# CurrentSensorAC712-30_multi.net
KiCad netlist of a schematic drawn in EAGLE
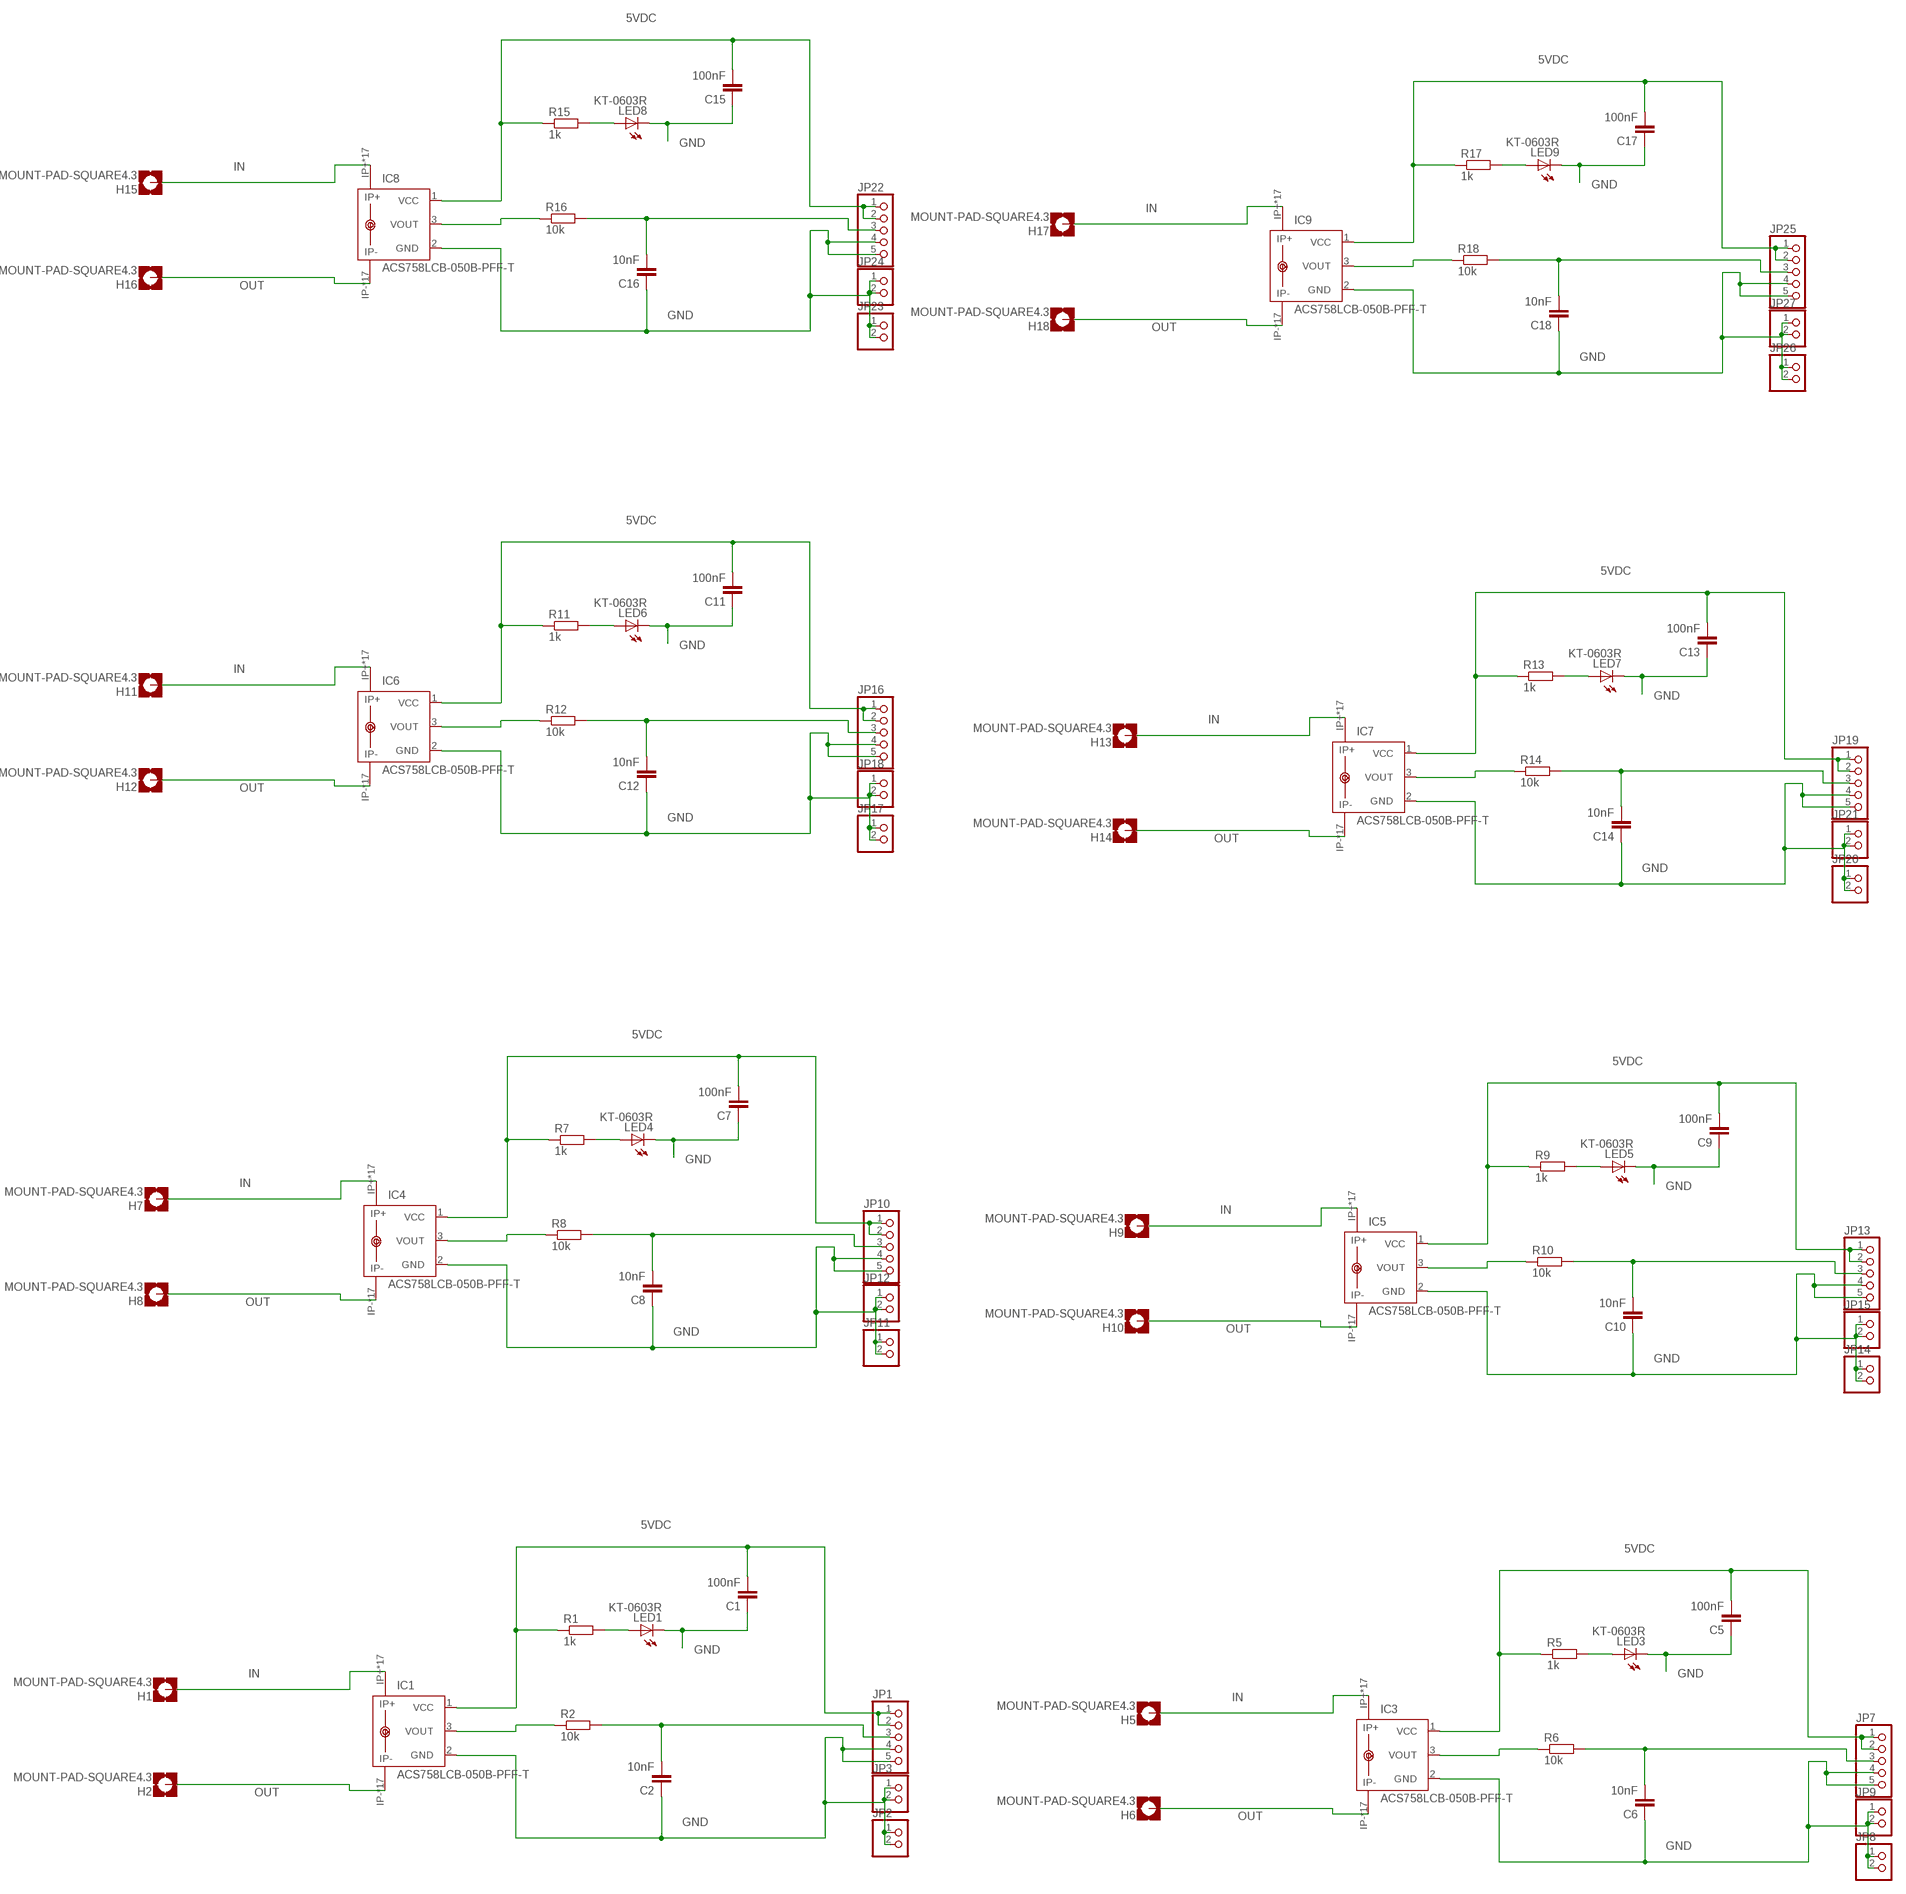
[diagram p0: schematic, sheet 1]

(export (version "E")
  (design (tool "Eeschema 10.0.6"))
  (components
    (comp (ref "C1")
      (value "100nF")
      (footprint "eagle-import:C0805")
      (libsource (lib "eagle-import") (part "C-EUC0805"))
    )
    (comp (ref "C2")
      (value "10nF")
      (footprint "eagle-import:C0805")
      (libsource (lib "eagle-import") (part "C-EUC0805"))
    )
    (comp (ref "C5")
      (value "100nF")
      (footprint "eagle-import:C0805")
      (libsource (lib "eagle-import") (part "C-EUC0805"))
    )
    (comp (ref "C6")
      (value "10nF")
      (footprint "eagle-import:C0805")
      (libsource (lib "eagle-import") (part "C-EUC0805"))
    )
    (comp (ref "C7")
      (value "100nF")
      (footprint "eagle-import:C0805")
      (libsource (lib "eagle-import") (part "C-EUC0805"))
    )
    (comp (ref "C8")
      (value "10nF")
      (footprint "eagle-import:C0805")
      (libsource (lib "eagle-import") (part "C-EUC0805"))
    )
    (comp (ref "C9")
      (value "100nF")
      (footprint "eagle-import:C0805")
      (libsource (lib "eagle-import") (part "C-EUC0805"))
    )
    (comp (ref "C10")
      (value "10nF")
      (footprint "eagle-import:C0805")
      (libsource (lib "eagle-import") (part "C-EUC0805"))
    )
    (comp (ref "C11")
      (value "100nF")
      (footprint "eagle-import:C0805")
      (libsource (lib "eagle-import") (part "C-EUC0805"))
    )
    (comp (ref "C12")
      (value "10nF")
      (footprint "eagle-import:C0805")
      (libsource (lib "eagle-import") (part "C-EUC0805"))
    )
    (comp (ref "C13")
      (value "100nF")
      (footprint "eagle-import:C0805")
      (libsource (lib "eagle-import") (part "C-EUC0805"))
    )
    (comp (ref "C14")
      (value "10nF")
      (footprint "eagle-import:C0805")
      (libsource (lib "eagle-import") (part "C-EUC0805"))
    )
    (comp (ref "C15")
      (value "100nF")
      (footprint "eagle-import:C0805")
      (libsource (lib "eagle-import") (part "C-EUC0805"))
    )
    (comp (ref "C16")
      (value "10nF")
      (footprint "eagle-import:C0805")
      (libsource (lib "eagle-import") (part "C-EUC0805"))
    )
    (comp (ref "C17")
      (value "100nF")
      (footprint "eagle-import:C0805")
      (libsource (lib "eagle-import") (part "C-EUC0805"))
    )
    (comp (ref "C18")
      (value "10nF")
      (footprint "eagle-import:C0805")
      (libsource (lib "eagle-import") (part "C-EUC0805"))
    )
    (comp (ref "H1")
      (value "MOUNT-PAD-SQUARE4.3")
      (footprint "eagle-import:4,3-PAD-SQUARE")
      (libsource (lib "eagle-import") (part "MOUNT-PAD-SQUARE4.3"))
    )
    (comp (ref "H2")
      (value "MOUNT-PAD-SQUARE4.3")
      (footprint "eagle-import:4,3-PAD-SQUARE")
      (libsource (lib "eagle-import") (part "MOUNT-PAD-SQUARE4.3"))
    )
    (comp (ref "H5")
      (value "MOUNT-PAD-SQUARE4.3")
      (footprint "eagle-import:4,3-PAD-SQUARE")
      (libsource (lib "eagle-import") (part "MOUNT-PAD-SQUARE4.3"))
    )
    (comp (ref "H6")
      (value "MOUNT-PAD-SQUARE4.3")
      (footprint "eagle-import:4,3-PAD-SQUARE")
      (libsource (lib "eagle-import") (part "MOUNT-PAD-SQUARE4.3"))
    )
    (comp (ref "H7")
      (value "MOUNT-PAD-SQUARE4.3")
      (footprint "eagle-import:4,3-PAD-SQUARE")
      (libsource (lib "eagle-import") (part "MOUNT-PAD-SQUARE4.3"))
    )
    (comp (ref "H8")
      (value "MOUNT-PAD-SQUARE4.3")
      (footprint "eagle-import:4,3-PAD-SQUARE")
      (libsource (lib "eagle-import") (part "MOUNT-PAD-SQUARE4.3"))
    )
    (comp (ref "H9")
      (value "MOUNT-PAD-SQUARE4.3")
      (footprint "eagle-import:4,3-PAD-SQUARE")
      (libsource (lib "eagle-import") (part "MOUNT-PAD-SQUARE4.3"))
    )
    (comp (ref "H10")
      (value "MOUNT-PAD-SQUARE4.3")
      (footprint "eagle-import:4,3-PAD-SQUARE")
      (libsource (lib "eagle-import") (part "MOUNT-PAD-SQUARE4.3"))
    )
    (comp (ref "H11")
      (value "MOUNT-PAD-SQUARE4.3")
      (footprint "eagle-import:4,3-PAD-SQUARE")
      (libsource (lib "eagle-import") (part "MOUNT-PAD-SQUARE4.3"))
    )
    (comp (ref "H12")
      (value "MOUNT-PAD-SQUARE4.3")
      (footprint "eagle-import:4,3-PAD-SQUARE")
      (libsource (lib "eagle-import") (part "MOUNT-PAD-SQUARE4.3"))
    )
    (comp (ref "H13")
      (value "MOUNT-PAD-SQUARE4.3")
      (footprint "eagle-import:4,3-PAD-SQUARE")
      (libsource (lib "eagle-import") (part "MOUNT-PAD-SQUARE4.3"))
    )
    (comp (ref "H14")
      (value "MOUNT-PAD-SQUARE4.3")
      (footprint "eagle-import:4,3-PAD-SQUARE")
      (libsource (lib "eagle-import") (part "MOUNT-PAD-SQUARE4.3"))
    )
    (comp (ref "H15")
      (value "MOUNT-PAD-SQUARE4.3")
      (footprint "eagle-import:4,3-PAD-SQUARE")
      (libsource (lib "eagle-import") (part "MOUNT-PAD-SQUARE4.3"))
    )
    (comp (ref "H16")
      (value "MOUNT-PAD-SQUARE4.3")
      (footprint "eagle-import:4,3-PAD-SQUARE")
      (libsource (lib "eagle-import") (part "MOUNT-PAD-SQUARE4.3"))
    )
    (comp (ref "H17")
      (value "MOUNT-PAD-SQUARE4.3")
      (footprint "eagle-import:4,3-PAD-SQUARE")
      (libsource (lib "eagle-import") (part "MOUNT-PAD-SQUARE4.3"))
    )
    (comp (ref "H18")
      (value "MOUNT-PAD-SQUARE4.3")
      (footprint "eagle-import:4,3-PAD-SQUARE")
      (libsource (lib "eagle-import") (part "MOUNT-PAD-SQUARE4.3"))
    )
    (comp (ref "IC1")
      (value "ACS758LCB-050B-PFF-T")
      (footprint "eagle-import:CB-PFF")
      (libsource (lib "eagle-import") (part "ACS758LCB-050B-PFF-T"))
    )
    (comp (ref "IC3")
      (value "ACS758LCB-050B-PFF-T")
      (footprint "eagle-import:CB-PFF")
      (libsource (lib "eagle-import") (part "ACS758LCB-050B-PFF-T"))
    )
    (comp (ref "IC4")
      (value "ACS758LCB-050B-PFF-T")
      (footprint "eagle-import:CB-PFF")
      (libsource (lib "eagle-import") (part "ACS758LCB-050B-PFF-T"))
    )
    (comp (ref "IC5")
      (value "ACS758LCB-050B-PFF-T")
      (footprint "eagle-import:CB-PFF")
      (libsource (lib "eagle-import") (part "ACS758LCB-050B-PFF-T"))
    )
    (comp (ref "IC6")
      (value "ACS758LCB-050B-PFF-T")
      (footprint "eagle-import:CB-PFF")
      (libsource (lib "eagle-import") (part "ACS758LCB-050B-PFF-T"))
    )
    (comp (ref "IC7")
      (value "ACS758LCB-050B-PFF-T")
      (footprint "eagle-import:CB-PFF")
      (libsource (lib "eagle-import") (part "ACS758LCB-050B-PFF-T"))
    )
    (comp (ref "IC8")
      (value "ACS758LCB-050B-PFF-T")
      (footprint "eagle-import:CB-PFF")
      (libsource (lib "eagle-import") (part "ACS758LCB-050B-PFF-T"))
    )
    (comp (ref "IC9")
      (value "ACS758LCB-050B-PFF-T")
      (footprint "eagle-import:CB-PFF")
      (libsource (lib "eagle-import") (part "ACS758LCB-050B-PFF-T"))
    )
    (comp (ref "JP1")
      (value "PINHD-1X5")
      (footprint "eagle-import:1X05")
      (libsource (lib "eagle-import") (part "PINHD-1X5"))
    )
    (comp (ref "JP2")
      (value "PINHD-1X2")
      (footprint "eagle-import:1X02")
      (libsource (lib "eagle-import") (part "PINHD-1X2"))
    )
    (comp (ref "JP3")
      (value "PINHD-1X2")
      (footprint "eagle-import:1X02")
      (libsource (lib "eagle-import") (part "PINHD-1X2"))
    )
    (comp (ref "JP7")
      (value "PINHD-1X5")
      (footprint "eagle-import:1X05")
      (libsource (lib "eagle-import") (part "PINHD-1X5"))
    )
    (comp (ref "JP8")
      (value "PINHD-1X2")
      (footprint "eagle-import:1X02")
      (libsource (lib "eagle-import") (part "PINHD-1X2"))
    )
    (comp (ref "JP9")
      (value "PINHD-1X2")
      (footprint "eagle-import:1X02")
      (libsource (lib "eagle-import") (part "PINHD-1X2"))
    )
    (comp (ref "JP10")
      (value "PINHD-1X5")
      (footprint "eagle-import:1X05")
      (libsource (lib "eagle-import") (part "PINHD-1X5"))
    )
    (comp (ref "JP11")
      (value "PINHD-1X2")
      (footprint "eagle-import:1X02")
      (libsource (lib "eagle-import") (part "PINHD-1X2"))
    )
    (comp (ref "JP12")
      (value "PINHD-1X2")
      (footprint "eagle-import:1X02")
      (libsource (lib "eagle-import") (part "PINHD-1X2"))
    )
    (comp (ref "JP13")
      (value "PINHD-1X5")
      (footprint "eagle-import:1X05")
      (libsource (lib "eagle-import") (part "PINHD-1X5"))
    )
    (comp (ref "JP14")
      (value "PINHD-1X2")
      (footprint "eagle-import:1X02")
      (libsource (lib "eagle-import") (part "PINHD-1X2"))
    )
    (comp (ref "JP15")
      (value "PINHD-1X2")
      (footprint "eagle-import:1X02")
      (libsource (lib "eagle-import") (part "PINHD-1X2"))
    )
    (comp (ref "JP16")
      (value "PINHD-1X5")
      (footprint "eagle-import:1X05")
      (libsource (lib "eagle-import") (part "PINHD-1X5"))
    )
    (comp (ref "JP17")
      (value "PINHD-1X2")
      (footprint "eagle-import:1X02")
      (libsource (lib "eagle-import") (part "PINHD-1X2"))
    )
    (comp (ref "JP18")
      (value "PINHD-1X2")
      (footprint "eagle-import:1X02")
      (libsource (lib "eagle-import") (part "PINHD-1X2"))
    )
    (comp (ref "JP19")
      (value "PINHD-1X5")
      (footprint "eagle-import:1X05")
      (libsource (lib "eagle-import") (part "PINHD-1X5"))
    )
    (comp (ref "JP20")
      (value "PINHD-1X2")
      (footprint "eagle-import:1X02")
      (libsource (lib "eagle-import") (part "PINHD-1X2"))
    )
    (comp (ref "JP21")
      (value "PINHD-1X2")
      (footprint "eagle-import:1X02")
      (libsource (lib "eagle-import") (part "PINHD-1X2"))
    )
    (comp (ref "JP22")
      (value "PINHD-1X5")
      (footprint "eagle-import:1X05")
      (libsource (lib "eagle-import") (part "PINHD-1X5"))
    )
    (comp (ref "JP23")
      (value "PINHD-1X2")
      (footprint "eagle-import:1X02")
      (libsource (lib "eagle-import") (part "PINHD-1X2"))
    )
    (comp (ref "JP24")
      (value "PINHD-1X2")
      (footprint "eagle-import:1X02")
      (libsource (lib "eagle-import") (part "PINHD-1X2"))
    )
    (comp (ref "JP25")
      (value "PINHD-1X5")
      (footprint "eagle-import:1X05")
      (libsource (lib "eagle-import") (part "PINHD-1X5"))
    )
    (comp (ref "JP26")
      (value "PINHD-1X2")
      (footprint "eagle-import:1X02")
      (libsource (lib "eagle-import") (part "PINHD-1X2"))
    )
    (comp (ref "JP27")
      (value "PINHD-1X2")
      (footprint "eagle-import:1X02")
      (libsource (lib "eagle-import") (part "PINHD-1X2"))
    )
    (comp (ref "LED1")
      (value "KT-0603R")
      (footprint "eagle-import:CHIPLED_0603")
      (libsource (lib "eagle-import") (part "LEDCHIPLED_0603"))
    )
    (comp (ref "LED3")
      (value "KT-0603R")
      (footprint "eagle-import:CHIPLED_0603")
      (libsource (lib "eagle-import") (part "LEDCHIPLED_0603"))
    )
    (comp (ref "LED4")
      (value "KT-0603R")
      (footprint "eagle-import:CHIPLED_0603")
      (libsource (lib "eagle-import") (part "LEDCHIPLED_0603"))
    )
    (comp (ref "LED5")
      (value "KT-0603R")
      (footprint "eagle-import:CHIPLED_0603")
      (libsource (lib "eagle-import") (part "LEDCHIPLED_0603"))
    )
    (comp (ref "LED6")
      (value "KT-0603R")
      (footprint "eagle-import:CHIPLED_0603")
      (libsource (lib "eagle-import") (part "LEDCHIPLED_0603"))
    )
    (comp (ref "LED7")
      (value "KT-0603R")
      (footprint "eagle-import:CHIPLED_0603")
      (libsource (lib "eagle-import") (part "LEDCHIPLED_0603"))
    )
    (comp (ref "LED8")
      (value "KT-0603R")
      (footprint "eagle-import:CHIPLED_0603")
      (libsource (lib "eagle-import") (part "LEDCHIPLED_0603"))
    )
    (comp (ref "LED9")
      (value "KT-0603R")
      (footprint "eagle-import:CHIPLED_0603")
      (libsource (lib "eagle-import") (part "LEDCHIPLED_0603"))
    )
    (comp (ref "R1")
      (value "1k")
      (footprint "eagle-import:R0805")
      (libsource (lib "eagle-import") (part "R-EU_R0805"))
    )
    (comp (ref "R2")
      (value "10k")
      (footprint "eagle-import:R0805")
      (libsource (lib "eagle-import") (part "R-EU_R0805"))
    )
    (comp (ref "R5")
      (value "1k")
      (footprint "eagle-import:R0805")
      (libsource (lib "eagle-import") (part "R-EU_R0805"))
    )
    (comp (ref "R6")
      (value "10k")
      (footprint "eagle-import:R0805")
      (libsource (lib "eagle-import") (part "R-EU_R0805"))
    )
    (comp (ref "R7")
      (value "1k")
      (footprint "eagle-import:R0805")
      (libsource (lib "eagle-import") (part "R-EU_R0805"))
    )
    (comp (ref "R8")
      (value "10k")
      (footprint "eagle-import:R0805")
      (libsource (lib "eagle-import") (part "R-EU_R0805"))
    )
    (comp (ref "R9")
      (value "1k")
      (footprint "eagle-import:R0805")
      (libsource (lib "eagle-import") (part "R-EU_R0805"))
    )
    (comp (ref "R10")
      (value "10k")
      (footprint "eagle-import:R0805")
      (libsource (lib "eagle-import") (part "R-EU_R0805"))
    )
    (comp (ref "R11")
      (value "1k")
      (footprint "eagle-import:R0805")
      (libsource (lib "eagle-import") (part "R-EU_R0805"))
    )
    (comp (ref "R12")
      (value "10k")
      (footprint "eagle-import:R0805")
      (libsource (lib "eagle-import") (part "R-EU_R0805"))
    )
    (comp (ref "R13")
      (value "1k")
      (footprint "eagle-import:R0805")
      (libsource (lib "eagle-import") (part "R-EU_R0805"))
    )
    (comp (ref "R14")
      (value "10k")
      (footprint "eagle-import:R0805")
      (libsource (lib "eagle-import") (part "R-EU_R0805"))
    )
    (comp (ref "R15")
      (value "1k")
      (footprint "eagle-import:R0805")
      (libsource (lib "eagle-import") (part "R-EU_R0805"))
    )
    (comp (ref "R16")
      (value "10k")
      (footprint "eagle-import:R0805")
      (libsource (lib "eagle-import") (part "R-EU_R0805"))
    )
    (comp (ref "R17")
      (value "1k")
      (footprint "eagle-import:R0805")
      (libsource (lib "eagle-import") (part "R-EU_R0805"))
    )
    (comp (ref "R18")
      (value "10k")
      (footprint "eagle-import:R0805")
      (libsource (lib "eagle-import") (part "R-EU_R0805"))
    )
  )
  (nets
    (net (code "1") (name "/5VDC") (class "Default")
      (node (ref "C1") (pin "2") (pinfunction "2_2") (pintype "passive"))
      (node (ref "C11") (pin "2") (pinfunction "2_2") (pintype "passive"))
      (node (ref "C13") (pin "2") (pinfunction "2_2") (pintype "passive"))
      (node (ref "C15") (pin "2") (pinfunction "2_2") (pintype "passive"))
      (node (ref "C17") (pin "2") (pinfunction "2_2") (pintype "passive"))
      (node (ref "C5") (pin "2") (pinfunction "2_2") (pintype "passive"))
      (node (ref "C7") (pin "2") (pinfunction "2_2") (pintype "passive"))
      (node (ref "C9") (pin "2") (pinfunction "2_2") (pintype "passive"))
      (node (ref "IC1") (pin "1") (pinfunction "VCC_1") (pintype "power_in"))
      (node (ref "IC3") (pin "1") (pinfunction "VCC_1") (pintype "power_in"))
      (node (ref "IC4") (pin "1") (pinfunction "VCC_1") (pintype "power_in"))
      (node (ref "IC5") (pin "1") (pinfunction "VCC_1") (pintype "power_in"))
      (node (ref "IC6") (pin "1") (pinfunction "VCC_1") (pintype "power_in"))
      (node (ref "IC7") (pin "1") (pinfunction "VCC_1") (pintype "power_in"))
      (node (ref "IC8") (pin "1") (pinfunction "VCC_1") (pintype "power_in"))
      (node (ref "IC9") (pin "1") (pinfunction "VCC_1") (pintype "power_in"))
      (node (ref "JP1") (pin "1") (pinfunction "1_1") (pintype "passive"))
      (node (ref "JP1") (pin "2") (pinfunction "2_2") (pintype "passive"))
      (node (ref "JP10") (pin "1") (pinfunction "1_1") (pintype "passive"))
      (node (ref "JP10") (pin "2") (pinfunction "2_2") (pintype "passive"))
      (node (ref "JP13") (pin "1") (pinfunction "1_1") (pintype "passive"))
      (node (ref "JP13") (pin "2") (pinfunction "2_2") (pintype "passive"))
      (node (ref "JP16") (pin "1") (pinfunction "1_1") (pintype "passive"))
      (node (ref "JP16") (pin "2") (pinfunction "2_2") (pintype "passive"))
      (node (ref "JP19") (pin "1") (pinfunction "1_1") (pintype "passive"))
      (node (ref "JP19") (pin "2") (pinfunction "2_2") (pintype "passive"))
      (node (ref "JP22") (pin "1") (pinfunction "1_1") (pintype "passive"))
      (node (ref "JP22") (pin "2") (pinfunction "2_2") (pintype "passive"))
      (node (ref "JP25") (pin "1") (pinfunction "1_1") (pintype "passive"))
      (node (ref "JP25") (pin "2") (pinfunction "2_2") (pintype "passive"))
      (node (ref "JP7") (pin "1") (pinfunction "1_1") (pintype "passive"))
      (node (ref "JP7") (pin "2") (pinfunction "2_2") (pintype "passive"))
      (node (ref "R1") (pin "1") (pinfunction "1_1") (pintype "passive"))
      (node (ref "R11") (pin "1") (pinfunction "1_1") (pintype "passive"))
      (node (ref "R13") (pin "1") (pinfunction "1_1") (pintype "passive"))
      (node (ref "R15") (pin "1") (pinfunction "1_1") (pintype "passive"))
      (node (ref "R17") (pin "1") (pinfunction "1_1") (pintype "passive"))
      (node (ref "R5") (pin "1") (pinfunction "1_1") (pintype "passive"))
      (node (ref "R7") (pin "1") (pinfunction "1_1") (pintype "passive"))
      (node (ref "R9") (pin "1") (pinfunction "1_1") (pintype "passive"))
    )
    (net (code "2") (name "/GND") (class "Default")
      (node (ref "C1") (pin "1") (pinfunction "1_1") (pintype "passive"))
      (node (ref "C10") (pin "1") (pinfunction "1_1") (pintype "passive"))
      (node (ref "C11") (pin "1") (pinfunction "1_1") (pintype "passive"))
      (node (ref "C12") (pin "1") (pinfunction "1_1") (pintype "passive"))
      (node (ref "C13") (pin "1") (pinfunction "1_1") (pintype "passive"))
      (node (ref "C14") (pin "1") (pinfunction "1_1") (pintype "passive"))
      (node (ref "C15") (pin "1") (pinfunction "1_1") (pintype "passive"))
      (node (ref "C16") (pin "1") (pinfunction "1_1") (pintype "passive"))
      (node (ref "C17") (pin "1") (pinfunction "1_1") (pintype "passive"))
      (node (ref "C18") (pin "1") (pinfunction "1_1") (pintype "passive"))
      (node (ref "C2") (pin "1") (pinfunction "1_1") (pintype "passive"))
      (node (ref "C5") (pin "1") (pinfunction "1_1") (pintype "passive"))
      (node (ref "C6") (pin "1") (pinfunction "1_1") (pintype "passive"))
      (node (ref "C7") (pin "1") (pinfunction "1_1") (pintype "passive"))
      (node (ref "C8") (pin "1") (pinfunction "1_1") (pintype "passive"))
      (node (ref "C9") (pin "1") (pinfunction "1_1") (pintype "passive"))
      (node (ref "IC1") (pin "2") (pinfunction "GND_2") (pintype "power_in"))
      (node (ref "IC3") (pin "2") (pinfunction "GND_2") (pintype "power_in"))
      (node (ref "IC4") (pin "2") (pinfunction "GND_2") (pintype "power_in"))
      (node (ref "IC5") (pin "2") (pinfunction "GND_2") (pintype "power_in"))
      (node (ref "IC6") (pin "2") (pinfunction "GND_2") (pintype "power_in"))
      (node (ref "IC7") (pin "2") (pinfunction "GND_2") (pintype "power_in"))
      (node (ref "IC8") (pin "2") (pinfunction "GND_2") (pintype "power_in"))
      (node (ref "IC9") (pin "2") (pinfunction "GND_2") (pintype "power_in"))
      (node (ref "JP1") (pin "4") (pinfunction "4_4") (pintype "passive"))
      (node (ref "JP1") (pin "5") (pinfunction "5_5") (pintype "passive"))
      (node (ref "JP10") (pin "4") (pinfunction "4_4") (pintype "passive"))
      (node (ref "JP10") (pin "5") (pinfunction "5_5") (pintype "passive"))
      (node (ref "JP11") (pin "1") (pinfunction "1_1") (pintype "passive"))
      (node (ref "JP11") (pin "2") (pinfunction "2_2") (pintype "passive"))
      (node (ref "JP12") (pin "1") (pinfunction "1_1") (pintype "passive"))
      (node (ref "JP12") (pin "2") (pinfunction "2_2") (pintype "passive"))
      (node (ref "JP13") (pin "4") (pinfunction "4_4") (pintype "passive"))
      (node (ref "JP13") (pin "5") (pinfunction "5_5") (pintype "passive"))
      (node (ref "JP14") (pin "1") (pinfunction "1_1") (pintype "passive"))
      (node (ref "JP14") (pin "2") (pinfunction "2_2") (pintype "passive"))
      (node (ref "JP15") (pin "1") (pinfunction "1_1") (pintype "passive"))
      (node (ref "JP15") (pin "2") (pinfunction "2_2") (pintype "passive"))
      (node (ref "JP16") (pin "4") (pinfunction "4_4") (pintype "passive"))
      (node (ref "JP16") (pin "5") (pinfunction "5_5") (pintype "passive"))
      (node (ref "JP17") (pin "1") (pinfunction "1_1") (pintype "passive"))
      (node (ref "JP17") (pin "2") (pinfunction "2_2") (pintype "passive"))
      (node (ref "JP18") (pin "1") (pinfunction "1_1") (pintype "passive"))
      (node (ref "JP18") (pin "2") (pinfunction "2_2") (pintype "passive"))
      (node (ref "JP19") (pin "4") (pinfunction "4_4") (pintype "passive"))
      (node (ref "JP19") (pin "5") (pinfunction "5_5") (pintype "passive"))
      (node (ref "JP2") (pin "1") (pinfunction "1_1") (pintype "passive"))
      (node (ref "JP2") (pin "2") (pinfunction "2_2") (pintype "passive"))
      (node (ref "JP20") (pin "1") (pinfunction "1_1") (pintype "passive"))
      (node (ref "JP20") (pin "2") (pinfunction "2_2") (pintype "passive"))
      (node (ref "JP21") (pin "1") (pinfunction "1_1") (pintype "passive"))
      (node (ref "JP21") (pin "2") (pinfunction "2_2") (pintype "passive"))
      (node (ref "JP22") (pin "4") (pinfunction "4_4") (pintype "passive"))
      (node (ref "JP22") (pin "5") (pinfunction "5_5") (pintype "passive"))
      (node (ref "JP23") (pin "1") (pinfunction "1_1") (pintype "passive"))
      (node (ref "JP23") (pin "2") (pinfunction "2_2") (pintype "passive"))
      (node (ref "JP24") (pin "1") (pinfunction "1_1") (pintype "passive"))
      (node (ref "JP24") (pin "2") (pinfunction "2_2") (pintype "passive"))
      (node (ref "JP25") (pin "4") (pinfunction "4_4") (pintype "passive"))
      (node (ref "JP25") (pin "5") (pinfunction "5_5") (pintype "passive"))
      (node (ref "JP26") (pin "1") (pinfunction "1_1") (pintype "passive"))
      (node (ref "JP26") (pin "2") (pinfunction "2_2") (pintype "passive"))
      (node (ref "JP27") (pin "1") (pinfunction "1_1") (pintype "passive"))
      (node (ref "JP27") (pin "2") (pinfunction "2_2") (pintype "passive"))
      (node (ref "JP3") (pin "1") (pinfunction "1_1") (pintype "passive"))
      (node (ref "JP3") (pin "2") (pinfunction "2_2") (pintype "passive"))
      (node (ref "JP7") (pin "4") (pinfunction "4_4") (pintype "passive"))
      (node (ref "JP7") (pin "5") (pinfunction "5_5") (pintype "passive"))
      (node (ref "JP8") (pin "1") (pinfunction "1_1") (pintype "passive"))
      (node (ref "JP8") (pin "2") (pinfunction "2_2") (pintype "passive"))
      (node (ref "JP9") (pin "1") (pinfunction "1_1") (pintype "passive"))
      (node (ref "JP9") (pin "2") (pinfunction "2_2") (pintype "passive"))
      (node (ref "LED1") (pin "C") (pinfunction "C_C") (pintype "passive"))
      (node (ref "LED3") (pin "C") (pinfunction "C_C") (pintype "passive"))
      (node (ref "LED4") (pin "C") (pinfunction "C_C") (pintype "passive"))
      (node (ref "LED5") (pin "C") (pinfunction "C_C") (pintype "passive"))
      (node (ref "LED6") (pin "C") (pinfunction "C_C") (pintype "passive"))
      (node (ref "LED7") (pin "C") (pinfunction "C_C") (pintype "passive"))
      (node (ref "LED8") (pin "C") (pinfunction "C_C") (pintype "passive"))
      (node (ref "LED9") (pin "C") (pinfunction "C_C") (pintype "passive"))
    )
    (net (code "3") (name "/IN") (class "Default")
      (node (ref "H1") (pin "B4,3") (pinfunction "MOUNT_B4,3") (pintype "passive"))
      (node (ref "H11") (pin "B4,3") (pinfunction "MOUNT_B4,3") (pintype "passive"))
      (node (ref "H13") (pin "B4,3") (pinfunction "MOUNT_B4,3") (pintype "passive"))
      (node (ref "H15") (pin "B4,3") (pinfunction "MOUNT_B4,3") (pintype "passive"))
      (node (ref "H17") (pin "B4,3") (pinfunction "MOUNT_B4,3") (pintype "passive"))
      (node (ref "H5") (pin "B4,3") (pinfunction "MOUNT_B4,3") (pintype "passive"))
      (node (ref "H7") (pin "B4,3") (pinfunction "MOUNT_B4,3") (pintype "passive"))
      (node (ref "H9") (pin "B4,3") (pinfunction "MOUNT_B4,3") (pintype "passive"))
      (node (ref "IC1") (pin "IP+") (pinfunction "IP+_IP+") (pintype "passive"))
      (node (ref "IC1") (pin "IP+@10") (pinfunction "IP+_IP+@10") (pintype "passive"))
      (node (ref "IC1") (pin "IP+@11") (pinfunction "IP+_IP+@11") (pintype "passive"))
      (node (ref "IC1") (pin "IP+@12") (pinfunction "IP+_IP+@12") (pintype "passive"))
      (node (ref "IC1") (pin "IP+@13") (pinfunction "IP+_IP+@13") (pintype "passive"))
      (node (ref "IC1") (pin "IP+@14") (pinfunction "IP+_IP+@14") (pintype "passive"))
      (node (ref "IC1") (pin "IP+@15") (pinfunction "IP+_IP+@15") (pintype "passive"))
      (node (ref "IC1") (pin "IP+@16") (pinfunction "IP+_IP+@16") (pintype "passive"))
      (node (ref "IC1") (pin "IP+@17") (pinfunction "IP+_IP+@17") (pintype "passive"))
      (node (ref "IC1") (pin "IP+@2") (pinfunction "IP+_IP+@2") (pintype "passive"))
      (node (ref "IC1") (pin "IP+@3") (pinfunction "IP+_IP+@3") (pintype "passive"))
      (node (ref "IC1") (pin "IP+@4") (pinfunction "IP+_IP+@4") (pintype "passive"))
      (node (ref "IC1") (pin "IP+@5") (pinfunction "IP+_IP+@5") (pintype "passive"))
      (node (ref "IC1") (pin "IP+@6") (pinfunction "IP+_IP+@6") (pintype "passive"))
      (node (ref "IC1") (pin "IP+@7") (pinfunction "IP+_IP+@7") (pintype "passive"))
      (node (ref "IC1") (pin "IP+@8") (pinfunction "IP+_IP+@8") (pintype "passive"))
      (node (ref "IC1") (pin "IP+@9") (pinfunction "IP+_IP+@9") (pintype "passive"))
      (node (ref "IC3") (pin "IP+") (pinfunction "IP+_IP+") (pintype "passive"))
      (node (ref "IC3") (pin "IP+@10") (pinfunction "IP+_IP+@10") (pintype "passive"))
      (node (ref "IC3") (pin "IP+@11") (pinfunction "IP+_IP+@11") (pintype "passive"))
      (node (ref "IC3") (pin "IP+@12") (pinfunction "IP+_IP+@12") (pintype "passive"))
      (node (ref "IC3") (pin "IP+@13") (pinfunction "IP+_IP+@13") (pintype "passive"))
      (node (ref "IC3") (pin "IP+@14") (pinfunction "IP+_IP+@14") (pintype "passive"))
      (node (ref "IC3") (pin "IP+@15") (pinfunction "IP+_IP+@15") (pintype "passive"))
      (node (ref "IC3") (pin "IP+@16") (pinfunction "IP+_IP+@16") (pintype "passive"))
      (node (ref "IC3") (pin "IP+@17") (pinfunction "IP+_IP+@17") (pintype "passive"))
      (node (ref "IC3") (pin "IP+@2") (pinfunction "IP+_IP+@2") (pintype "passive"))
      (node (ref "IC3") (pin "IP+@3") (pinfunction "IP+_IP+@3") (pintype "passive"))
      (node (ref "IC3") (pin "IP+@4") (pinfunction "IP+_IP+@4") (pintype "passive"))
      (node (ref "IC3") (pin "IP+@5") (pinfunction "IP+_IP+@5") (pintype "passive"))
      (node (ref "IC3") (pin "IP+@6") (pinfunction "IP+_IP+@6") (pintype "passive"))
      (node (ref "IC3") (pin "IP+@7") (pinfunction "IP+_IP+@7") (pintype "passive"))
      (node (ref "IC3") (pin "IP+@8") (pinfunction "IP+_IP+@8") (pintype "passive"))
      (node (ref "IC3") (pin "IP+@9") (pinfunction "IP+_IP+@9") (pintype "passive"))
      (node (ref "IC4") (pin "IP+") (pinfunction "IP+_IP+") (pintype "passive"))
      (node (ref "IC4") (pin "IP+@10") (pinfunction "IP+_IP+@10") (pintype "passive"))
      (node (ref "IC4") (pin "IP+@11") (pinfunction "IP+_IP+@11") (pintype "passive"))
      (node (ref "IC4") (pin "IP+@12") (pinfunction "IP+_IP+@12") (pintype "passive"))
      (node (ref "IC4") (pin "IP+@13") (pinfunction "IP+_IP+@13") (pintype "passive"))
      (node (ref "IC4") (pin "IP+@14") (pinfunction "IP+_IP+@14") (pintype "passive"))
      (node (ref "IC4") (pin "IP+@15") (pinfunction "IP+_IP+@15") (pintype "passive"))
      (node (ref "IC4") (pin "IP+@16") (pinfunction "IP+_IP+@16") (pintype "passive"))
      (node (ref "IC4") (pin "IP+@17") (pinfunction "IP+_IP+@17") (pintype "passive"))
      (node (ref "IC4") (pin "IP+@2") (pinfunction "IP+_IP+@2") (pintype "passive"))
      (node (ref "IC4") (pin "IP+@3") (pinfunction "IP+_IP+@3") (pintype "passive"))
      (node (ref "IC4") (pin "IP+@4") (pinfunction "IP+_IP+@4") (pintype "passive"))
      (node (ref "IC4") (pin "IP+@5") (pinfunction "IP+_IP+@5") (pintype "passive"))
      (node (ref "IC4") (pin "IP+@6") (pinfunction "IP+_IP+@6") (pintype "passive"))
      (node (ref "IC4") (pin "IP+@7") (pinfunction "IP+_IP+@7") (pintype "passive"))
      (node (ref "IC4") (pin "IP+@8") (pinfunction "IP+_IP+@8") (pintype "passive"))
      (node (ref "IC4") (pin "IP+@9") (pinfunction "IP+_IP+@9") (pintype "passive"))
      (node (ref "IC5") (pin "IP+") (pinfunction "IP+_IP+") (pintype "passive"))
      (node (ref "IC5") (pin "IP+@10") (pinfunction "IP+_IP+@10") (pintype "passive"))
      (node (ref "IC5") (pin "IP+@11") (pinfunction "IP+_IP+@11") (pintype "passive"))
      (node (ref "IC5") (pin "IP+@12") (pinfunction "IP+_IP+@12") (pintype "passive"))
      (node (ref "IC5") (pin "IP+@13") (pinfunction "IP+_IP+@13") (pintype "passive"))
      (node (ref "IC5") (pin "IP+@14") (pinfunction "IP+_IP+@14") (pintype "passive"))
      (node (ref "IC5") (pin "IP+@15") (pinfunction "IP+_IP+@15") (pintype "passive"))
      (node (ref "IC5") (pin "IP+@16") (pinfunction "IP+_IP+@16") (pintype "passive"))
      (node (ref "IC5") (pin "IP+@17") (pinfunction "IP+_IP+@17") (pintype "passive"))
      (node (ref "IC5") (pin "IP+@2") (pinfunction "IP+_IP+@2") (pintype "passive"))
      (node (ref "IC5") (pin "IP+@3") (pinfunction "IP+_IP+@3") (pintype "passive"))
      (node (ref "IC5") (pin "IP+@4") (pinfunction "IP+_IP+@4") (pintype "passive"))
      (node (ref "IC5") (pin "IP+@5") (pinfunction "IP+_IP+@5") (pintype "passive"))
      (node (ref "IC5") (pin "IP+@6") (pinfunction "IP+_IP+@6") (pintype "passive"))
      (node (ref "IC5") (pin "IP+@7") (pinfunction "IP+_IP+@7") (pintype "passive"))
      (node (ref "IC5") (pin "IP+@8") (pinfunction "IP+_IP+@8") (pintype "passive"))
      (node (ref "IC5") (pin "IP+@9") (pinfunction "IP+_IP+@9") (pintype "passive"))
      (node (ref "IC6") (pin "IP+") (pinfunction "IP+_IP+") (pintype "passive"))
      (node (ref "IC6") (pin "IP+@10") (pinfunction "IP+_IP+@10") (pintype "passive"))
      (node (ref "IC6") (pin "IP+@11") (pinfunction "IP+_IP+@11") (pintype "passive"))
      (node (ref "IC6") (pin "IP+@12") (pinfunction "IP+_IP+@12") (pintype "passive"))
      (node (ref "IC6") (pin "IP+@13") (pinfunction "IP+_IP+@13") (pintype "passive"))
      (node (ref "IC6") (pin "IP+@14") (pinfunction "IP+_IP+@14") (pintype "passive"))
      (node (ref "IC6") (pin "IP+@15") (pinfunction "IP+_IP+@15") (pintype "passive"))
      (node (ref "IC6") (pin "IP+@16") (pinfunction "IP+_IP+@16") (pintype "passive"))
      (node (ref "IC6") (pin "IP+@17") (pinfunction "IP+_IP+@17") (pintype "passive"))
      (node (ref "IC6") (pin "IP+@2") (pinfunction "IP+_IP+@2") (pintype "passive"))
      (node (ref "IC6") (pin "IP+@3") (pinfunction "IP+_IP+@3") (pintype "passive"))
      (node (ref "IC6") (pin "IP+@4") (pinfunction "IP+_IP+@4") (pintype "passive"))
      (node (ref "IC6") (pin "IP+@5") (pinfunction "IP+_IP+@5") (pintype "passive"))
      (node (ref "IC6") (pin "IP+@6") (pinfunction "IP+_IP+@6") (pintype "passive"))
      (node (ref "IC6") (pin "IP+@7") (pinfunction "IP+_IP+@7") (pintype "passive"))
      (node (ref "IC6") (pin "IP+@8") (pinfunction "IP+_IP+@8") (pintype "passive"))
      (node (ref "IC6") (pin "IP+@9") (pinfunction "IP+_IP+@9") (pintype "passive"))
      (node (ref "IC7") (pin "IP+") (pinfunction "IP+_IP+") (pintype "passive"))
      (node (ref "IC7") (pin "IP+@10") (pinfunction "IP+_IP+@10") (pintype "passive"))
      (node (ref "IC7") (pin "IP+@11") (pinfunction "IP+_IP+@11") (pintype "passive"))
      (node (ref "IC7") (pin "IP+@12") (pinfunction "IP+_IP+@12") (pintype "passive"))
      (node (ref "IC7") (pin "IP+@13") (pinfunction "IP+_IP+@13") (pintype "passive"))
      (node (ref "IC7") (pin "IP+@14") (pinfunction "IP+_IP+@14") (pintype "passive"))
      (node (ref "IC7") (pin "IP+@15") (pinfunction "IP+_IP+@15") (pintype "passive"))
      (node (ref "IC7") (pin "IP+@16") (pinfunction "IP+_IP+@16") (pintype "passive"))
      (node (ref "IC7") (pin "IP+@17") (pinfunction "IP+_IP+@17") (pintype "passive"))
      (node (ref "IC7") (pin "IP+@2") (pinfunction "IP+_IP+@2") (pintype "passive"))
      (node (ref "IC7") (pin "IP+@3") (pinfunction "IP+_IP+@3") (pintype "passive"))
      (node (ref "IC7") (pin "IP+@4") (pinfunction "IP+_IP+@4") (pintype "passive"))
      (node (ref "IC7") (pin "IP+@5") (pinfunction "IP+_IP+@5") (pintype "passive"))
      (node (ref "IC7") (pin "IP+@6") (pinfunction "IP+_IP+@6") (pintype "passive"))
      (node (ref "IC7") (pin "IP+@7") (pinfunction "IP+_IP+@7") (pintype "passive"))
      (node (ref "IC7") (pin "IP+@8") (pinfunction "IP+_IP+@8") (pintype "passive"))
      (node (ref "IC7") (pin "IP+@9") (pinfunction "IP+_IP+@9") (pintype "passive"))
      (node (ref "IC8") (pin "IP+") (pinfunction "IP+_IP+") (pintype "passive"))
      (node (ref "IC8") (pin "IP+@10") (pinfunction "IP+_IP+@10") (pintype "passive"))
      (node (ref "IC8") (pin "IP+@11") (pinfunction "IP+_IP+@11") (pintype "passive"))
      (node (ref "IC8") (pin "IP+@12") (pinfunction "IP+_IP+@12") (pintype "passive"))
      (node (ref "IC8") (pin "IP+@13") (pinfunction "IP+_IP+@13") (pintype "passive"))
      (node (ref "IC8") (pin "IP+@14") (pinfunction "IP+_IP+@14") (pintype "passive"))
      (node (ref "IC8") (pin "IP+@15") (pinfunction "IP+_IP+@15") (pintype "passive"))
      (node (ref "IC8") (pin "IP+@16") (pinfunction "IP+_IP+@16") (pintype "passive"))
      (node (ref "IC8") (pin "IP+@17") (pinfunction "IP+_IP+@17") (pintype "passive"))
      (node (ref "IC8") (pin "IP+@2") (pinfunction "IP+_IP+@2") (pintype "passive"))
      (node (ref "IC8") (pin "IP+@3") (pinfunction "IP+_IP+@3") (pintype "passive"))
      (node (ref "IC8") (pin "IP+@4") (pinfunction "IP+_IP+@4") (pintype "passive"))
      (node (ref "IC8") (pin "IP+@5") (pinfunction "IP+_IP+@5") (pintype "passive"))
      (node (ref "IC8") (pin "IP+@6") (pinfunction "IP+_IP+@6") (pintype "passive"))
      (node (ref "IC8") (pin "IP+@7") (pinfunction "IP+_IP+@7") (pintype "passive"))
      (node (ref "IC8") (pin "IP+@8") (pinfunction "IP+_IP+@8") (pintype "passive"))
      (node (ref "IC8") (pin "IP+@9") (pinfunction "IP+_IP+@9") (pintype "passive"))
      (node (ref "IC9") (pin "IP+") (pinfunction "IP+_IP+") (pintype "passive"))
      (node (ref "IC9") (pin "IP+@10") (pinfunction "IP+_IP+@10") (pintype "passive"))
      (node (ref "IC9") (pin "IP+@11") (pinfunction "IP+_IP+@11") (pintype "passive"))
      (node (ref "IC9") (pin "IP+@12") (pinfunction "IP+_IP+@12") (pintype "passive"))
      (node (ref "IC9") (pin "IP+@13") (pinfunction "IP+_IP+@13") (pintype "passive"))
      (node (ref "IC9") (pin "IP+@14") (pinfunction "IP+_IP+@14") (pintype "passive"))
      (node (ref "IC9") (pin "IP+@15") (pinfunction "IP+_IP+@15") (pintype "passive"))
      (node (ref "IC9") (pin "IP+@16") (pinfunction "IP+_IP+@16") (pintype "passive"))
      (node (ref "IC9") (pin "IP+@17") (pinfunction "IP+_IP+@17") (pintype "passive"))
      (node (ref "IC9") (pin "IP+@2") (pinfunction "IP+_IP+@2") (pintype "passive"))
      (node (ref "IC9") (pin "IP+@3") (pinfunction "IP+_IP+@3") (pintype "passive"))
      (node (ref "IC9") (pin "IP+@4") (pinfunction "IP+_IP+@4") (pintype "passive"))
      (node (ref "IC9") (pin "IP+@5") (pinfunction "IP+_IP+@5") (pintype "passive"))
      (node (ref "IC9") (pin "IP+@6") (pinfunction "IP+_IP+@6") (pintype "passive"))
      (node (ref "IC9") (pin "IP+@7") (pinfunction "IP+_IP+@7") (pintype "passive"))
      (node (ref "IC9") (pin "IP+@8") (pinfunction "IP+_IP+@8") (pintype "passive"))
      (node (ref "IC9") (pin "IP+@9") (pinfunction "IP+_IP+@9") (pintype "passive"))
    )
    (net (code "4") (name "/OUT") (class "Default")
      (node (ref "H10") (pin "B4,3") (pinfunction "MOUNT_B4,3") (pintype "passive"))
      (node (ref "H12") (pin "B4,3") (pinfunction "MOUNT_B4,3") (pintype "passive"))
      (node (ref "H14") (pin "B4,3") (pinfunction "MOUNT_B4,3") (pintype "passive"))
      (node (ref "H16") (pin "B4,3") (pinfunction "MOUNT_B4,3") (pintype "passive"))
      (node (ref "H18") (pin "B4,3") (pinfunction "MOUNT_B4,3") (pintype "passive"))
      (node (ref "H2") (pin "B4,3") (pinfunction "MOUNT_B4,3") (pintype "passive"))
      (node (ref "H6") (pin "B4,3") (pinfunction "MOUNT_B4,3") (pintype "passive"))
      (node (ref "H8") (pin "B4,3") (pinfunction "MOUNT_B4,3") (pintype "passive"))
      (node (ref "IC1") (pin "IP-") (pinfunction "IP-_IP-") (pintype "passive"))
      (node (ref "IC1") (pin "IP-@10") (pinfunction "IP-_IP-@10") (pintype "passive"))
      (node (ref "IC1") (pin "IP-@11") (pinfunction "IP-_IP-@11") (pintype "passive"))
      (node (ref "IC1") (pin "IP-@12") (pinfunction "IP-_IP-@12") (pintype "passive"))
      (node (ref "IC1") (pin "IP-@13") (pinfunction "IP-_IP-@13") (pintype "passive"))
      (node (ref "IC1") (pin "IP-@14") (pinfunction "IP-_IP-@14") (pintype "passive"))
      (node (ref "IC1") (pin "IP-@15") (pinfunction "IP-_IP-@15") (pintype "passive"))
      (node (ref "IC1") (pin "IP-@16") (pinfunction "IP-_IP-@16") (pintype "passive"))
      (node (ref "IC1") (pin "IP-@17") (pinfunction "IP-_IP-@17") (pintype "passive"))
      (node (ref "IC1") (pin "IP-@2") (pinfunction "IP-_IP-@2") (pintype "passive"))
      (node (ref "IC1") (pin "IP-@3") (pinfunction "IP-_IP-@3") (pintype "passive"))
      (node (ref "IC1") (pin "IP-@4") (pinfunction "IP-_IP-@4") (pintype "passive"))
      (node (ref "IC1") (pin "IP-@5") (pinfunction "IP-_IP-@5") (pintype "passive"))
      (node (ref "IC1") (pin "IP-@6") (pinfunction "IP-_IP-@6") (pintype "passive"))
      (node (ref "IC1") (pin "IP-@7") (pinfunction "IP-_IP-@7") (pintype "passive"))
      (node (ref "IC1") (pin "IP-@8") (pinfunction "IP-_IP-@8") (pintype "passive"))
      (node (ref "IC1") (pin "IP-@9") (pinfunction "IP-_IP-@9") (pintype "passive"))
      (node (ref "IC3") (pin "IP-") (pinfunction "IP-_IP-") (pintype "passive"))
      (node (ref "IC3") (pin "IP-@10") (pinfunction "IP-_IP-@10") (pintype "passive"))
      (node (ref "IC3") (pin "IP-@11") (pinfunction "IP-_IP-@11") (pintype "passive"))
      (node (ref "IC3") (pin "IP-@12") (pinfunction "IP-_IP-@12") (pintype "passive"))
      (node (ref "IC3") (pin "IP-@13") (pinfunction "IP-_IP-@13") (pintype "passive"))
      (node (ref "IC3") (pin "IP-@14") (pinfunction "IP-_IP-@14") (pintype "passive"))
      (node (ref "IC3") (pin "IP-@15") (pinfunction "IP-_IP-@15") (pintype "passive"))
      (node (ref "IC3") (pin "IP-@16") (pinfunction "IP-_IP-@16") (pintype "passive"))
      (node (ref "IC3") (pin "IP-@17") (pinfunction "IP-_IP-@17") (pintype "passive"))
      (node (ref "IC3") (pin "IP-@2") (pinfunction "IP-_IP-@2") (pintype "passive"))
      (node (ref "IC3") (pin "IP-@3") (pinfunction "IP-_IP-@3") (pintype "passive"))
      (node (ref "IC3") (pin "IP-@4") (pinfunction "IP-_IP-@4") (pintype "passive"))
      (node (ref "IC3") (pin "IP-@5") (pinfunction "IP-_IP-@5") (pintype "passive"))
      (node (ref "IC3") (pin "IP-@6") (pinfunction "IP-_IP-@6") (pintype "passive"))
      (node (ref "IC3") (pin "IP-@7") (pinfunction "IP-_IP-@7") (pintype "passive"))
      (node (ref "IC3") (pin "IP-@8") (pinfunction "IP-_IP-@8") (pintype "passive"))
      (node (ref "IC3") (pin "IP-@9") (pinfunction "IP-_IP-@9") (pintype "passive"))
      (node (ref "IC4") (pin "IP-") (pinfunction "IP-_IP-") (pintype "passive"))
      (node (ref "IC4") (pin "IP-@10") (pinfunction "IP-_IP-@10") (pintype "passive"))
      (node (ref "IC4") (pin "IP-@11") (pinfunction "IP-_IP-@11") (pintype "passive"))
      (node (ref "IC4") (pin "IP-@12") (pinfunction "IP-_IP-@12") (pintype "passive"))
      (node (ref "IC4") (pin "IP-@13") (pinfunction "IP-_IP-@13") (pintype "passive"))
      (node (ref "IC4") (pin "IP-@14") (pinfunction "IP-_IP-@14") (pintype "passive"))
      (node (ref "IC4") (pin "IP-@15") (pinfunction "IP-_IP-@15") (pintype "passive"))
      (node (ref "IC4") (pin "IP-@16") (pinfunction "IP-_IP-@16") (pintype "passive"))
      (node (ref "IC4") (pin "IP-@17") (pinfunction "IP-_IP-@17") (pintype "passive"))
      (node (ref "IC4") (pin "IP-@2") (pinfunction "IP-_IP-@2") (pintype "passive"))
      (node (ref "IC4") (pin "IP-@3") (pinfunction "IP-_IP-@3") (pintype "passive"))
      (node (ref "IC4") (pin "IP-@4") (pinfunction "IP-_IP-@4") (pintype "passive"))
      (node (ref "IC4") (pin "IP-@5") (pinfunction "IP-_IP-@5") (pintype "passive"))
      (node (ref "IC4") (pin "IP-@6") (pinfunction "IP-_IP-@6") (pintype "passive"))
      (node (ref "IC4") (pin "IP-@7") (pinfunction "IP-_IP-@7") (pintype "passive"))
      (node (ref "IC4") (pin "IP-@8") (pinfunction "IP-_IP-@8") (pintype "passive"))
      (node (ref "IC4") (pin "IP-@9") (pinfunction "IP-_IP-@9") (pintype "passive"))
      (node (ref "IC5") (pin "IP-") (pinfunction "IP-_IP-") (pintype "passive"))
      (node (ref "IC5") (pin "IP-@10") (pinfunction "IP-_IP-@10") (pintype "passive"))
      (node (ref "IC5") (pin "IP-@11") (pinfunction "IP-_IP-@11") (pintype "passive"))
      (node (ref "IC5") (pin "IP-@12") (pinfunction "IP-_IP-@12") (pintype "passive"))
      (node (ref "IC5") (pin "IP-@13") (pinfunction "IP-_IP-@13") (pintype "passive"))
      (node (ref "IC5") (pin "IP-@14") (pinfunction "IP-_IP-@14") (pintype "passive"))
      (node (ref "IC5") (pin "IP-@15") (pinfunction "IP-_IP-@15") (pintype "passive"))
      (node (ref "IC5") (pin "IP-@16") (pinfunction "IP-_IP-@16") (pintype "passive"))
      (node (ref "IC5") (pin "IP-@17") (pinfunction "IP-_IP-@17") (pintype "passive"))
      (node (ref "IC5") (pin "IP-@2") (pinfunction "IP-_IP-@2") (pintype "passive"))
      (node (ref "IC5") (pin "IP-@3") (pinfunction "IP-_IP-@3") (pintype "passive"))
      (node (ref "IC5") (pin "IP-@4") (pinfunction "IP-_IP-@4") (pintype "passive"))
      (node (ref "IC5") (pin "IP-@5") (pinfunction "IP-_IP-@5") (pintype "passive"))
      (node (ref "IC5") (pin "IP-@6") (pinfunction "IP-_IP-@6") (pintype "passive"))
      (node (ref "IC5") (pin "IP-@7") (pinfunction "IP-_IP-@7") (pintype "passive"))
      (node (ref "IC5") (pin "IP-@8") (pinfunction "IP-_IP-@8") (pintype "passive"))
      (node (ref "IC5") (pin "IP-@9") (pinfunction "IP-_IP-@9") (pintype "passive"))
      (node (ref "IC6") (pin "IP-") (pinfunction "IP-_IP-") (pintype "passive"))
      (node (ref "IC6") (pin "IP-@10") (pinfunction "IP-_IP-@10") (pintype "passive"))
      (node (ref "IC6") (pin "IP-@11") (pinfunction "IP-_IP-@11") (pintype "passive"))
      (node (ref "IC6") (pin "IP-@12") (pinfunction "IP-_IP-@12") (pintype "passive"))
      (node (ref "IC6") (pin "IP-@13") (pinfunction "IP-_IP-@13") (pintype "passive"))
      (node (ref "IC6") (pin "IP-@14") (pinfunction "IP-_IP-@14") (pintype "passive"))
      (node (ref "IC6") (pin "IP-@15") (pinfunction "IP-_IP-@15") (pintype "passive"))
      (node (ref "IC6") (pin "IP-@16") (pinfunction "IP-_IP-@16") (pintype "passive"))
      (node (ref "IC6") (pin "IP-@17") (pinfunction "IP-_IP-@17") (pintype "passive"))
      (node (ref "IC6") (pin "IP-@2") (pinfunction "IP-_IP-@2") (pintype "passive"))
      (node (ref "IC6") (pin "IP-@3") (pinfunction "IP-_IP-@3") (pintype "passive"))
      (node (ref "IC6") (pin "IP-@4") (pinfunction "IP-_IP-@4") (pintype "passive"))
      (node (ref "IC6") (pin "IP-@5") (pinfunction "IP-_IP-@5") (pintype "passive"))
      (node (ref "IC6") (pin "IP-@6") (pinfunction "IP-_IP-@6") (pintype "passive"))
      (node (ref "IC6") (pin "IP-@7") (pinfunction "IP-_IP-@7") (pintype "passive"))
      (node (ref "IC6") (pin "IP-@8") (pinfunction "IP-_IP-@8") (pintype "passive"))
      (node (ref "IC6") (pin "IP-@9") (pinfunction "IP-_IP-@9") (pintype "passive"))
      (node (ref "IC7") (pin "IP-") (pinfunction "IP-_IP-") (pintype "passive"))
      (node (ref "IC7") (pin "IP-@10") (pinfunction "IP-_IP-@10") (pintype "passive"))
      (node (ref "IC7") (pin "IP-@11") (pinfunction "IP-_IP-@11") (pintype "passive"))
      (node (ref "IC7") (pin "IP-@12") (pinfunction "IP-_IP-@12") (pintype "passive"))
      (node (ref "IC7") (pin "IP-@13") (pinfunction "IP-_IP-@13") (pintype "passive"))
      (node (ref "IC7") (pin "IP-@14") (pinfunction "IP-_IP-@14") (pintype "passive"))
      (node (ref "IC7") (pin "IP-@15") (pinfunction "IP-_IP-@15") (pintype "passive"))
      (node (ref "IC7") (pin "IP-@16") (pinfunction "IP-_IP-@16") (pintype "passive"))
      (node (ref "IC7") (pin "IP-@17") (pinfunction "IP-_IP-@17") (pintype "passive"))
      (node (ref "IC7") (pin "IP-@2") (pinfunction "IP-_IP-@2") (pintype "passive"))
      (node (ref "IC7") (pin "IP-@3") (pinfunction "IP-_IP-@3") (pintype "passive"))
      (node (ref "IC7") (pin "IP-@4") (pinfunction "IP-_IP-@4") (pintype "passive"))
      (node (ref "IC7") (pin "IP-@5") (pinfunction "IP-_IP-@5") (pintype "passive"))
      (node (ref "IC7") (pin "IP-@6") (pinfunction "IP-_IP-@6") (pintype "passive"))
      (node (ref "IC7") (pin "IP-@7") (pinfunction "IP-_IP-@7") (pintype "passive"))
      (node (ref "IC7") (pin "IP-@8") (pinfunction "IP-_IP-@8") (pintype "passive"))
      (node (ref "IC7") (pin "IP-@9") (pinfunction "IP-_IP-@9") (pintype "passive"))
      (node (ref "IC8") (pin "IP-") (pinfunction "IP-_IP-") (pintype "passive"))
      (node (ref "IC8") (pin "IP-@10") (pinfunction "IP-_IP-@10") (pintype "passive"))
      (node (ref "IC8") (pin "IP-@11") (pinfunction "IP-_IP-@11") (pintype "passive"))
      (node (ref "IC8") (pin "IP-@12") (pinfunction "IP-_IP-@12") (pintype "passive"))
      (node (ref "IC8") (pin "IP-@13") (pinfunction "IP-_IP-@13") (pintype "passive"))
      (node (ref "IC8") (pin "IP-@14") (pinfunction "IP-_IP-@14") (pintype "passive"))
      (node (ref "IC8") (pin "IP-@15") (pinfunction "IP-_IP-@15") (pintype "passive"))
      (node (ref "IC8") (pin "IP-@16") (pinfunction "IP-_IP-@16") (pintype "passive"))
      (node (ref "IC8") (pin "IP-@17") (pinfunction "IP-_IP-@17") (pintype "passive"))
      (node (ref "IC8") (pin "IP-@2") (pinfunction "IP-_IP-@2") (pintype "passive"))
      (node (ref "IC8") (pin "IP-@3") (pinfunction "IP-_IP-@3") (pintype "passive"))
      (node (ref "IC8") (pin "IP-@4") (pinfunction "IP-_IP-@4") (pintype "passive"))
      (node (ref "IC8") (pin "IP-@5") (pinfunction "IP-_IP-@5") (pintype "passive"))
      (node (ref "IC8") (pin "IP-@6") (pinfunction "IP-_IP-@6") (pintype "passive"))
      (node (ref "IC8") (pin "IP-@7") (pinfunction "IP-_IP-@7") (pintype "passive"))
      (node (ref "IC8") (pin "IP-@8") (pinfunction "IP-_IP-@8") (pintype "passive"))
      (node (ref "IC8") (pin "IP-@9") (pinfunction "IP-_IP-@9") (pintype "passive"))
      (node (ref "IC9") (pin "IP-") (pinfunction "IP-_IP-") (pintype "passive"))
      (node (ref "IC9") (pin "IP-@10") (pinfunction "IP-_IP-@10") (pintype "passive"))
      (node (ref "IC9") (pin "IP-@11") (pinfunction "IP-_IP-@11") (pintype "passive"))
      (node (ref "IC9") (pin "IP-@12") (pinfunction "IP-_IP-@12") (pintype "passive"))
      (node (ref "IC9") (pin "IP-@13") (pinfunction "IP-_IP-@13") (pintype "passive"))
      (node (ref "IC9") (pin "IP-@14") (pinfunction "IP-_IP-@14") (pintype "passive"))
      (node (ref "IC9") (pin "IP-@15") (pinfunction "IP-_IP-@15") (pintype "passive"))
      (node (ref "IC9") (pin "IP-@16") (pinfunction "IP-_IP-@16") (pintype "passive"))
      (node (ref "IC9") (pin "IP-@17") (pinfunction "IP-_IP-@17") (pintype "passive"))
      (node (ref "IC9") (pin "IP-@2") (pinfunction "IP-_IP-@2") (pintype "passive"))
      (node (ref "IC9") (pin "IP-@3") (pinfunction "IP-_IP-@3") (pintype "passive"))
      (node (ref "IC9") (pin "IP-@4") (pinfunction "IP-_IP-@4") (pintype "passive"))
      (node (ref "IC9") (pin "IP-@5") (pinfunction "IP-_IP-@5") (pintype "passive"))
      (node (ref "IC9") (pin "IP-@6") (pinfunction "IP-_IP-@6") (pintype "passive"))
      (node (ref "IC9") (pin "IP-@7") (pinfunction "IP-_IP-@7") (pintype "passive"))
      (node (ref "IC9") (pin "IP-@8") (pinfunction "IP-_IP-@8") (pintype "passive"))
      (node (ref "IC9") (pin "IP-@9") (pinfunction "IP-_IP-@9") (pintype "passive"))
    )
    (net (code "5") (name "Net-(C2-Pad2)") (class "Default")
      (node (ref "C2") (pin "2") (pinfunction "2_2") (pintype "passive"))
      (node (ref "JP1") (pin "3") (pinfunction "3_3") (pintype "passive"))
      (node (ref "R2") (pin "2") (pinfunction "2_2") (pintype "passive"))
    )
    (net (code "6") (name "Net-(C6-Pad2)") (class "Default")
      (node (ref "C6") (pin "2") (pinfunction "2_2") (pintype "passive"))
      (node (ref "JP7") (pin "3") (pinfunction "3_3") (pintype "passive"))
      (node (ref "R6") (pin "2") (pinfunction "2_2") (pintype "passive"))
    )
    (net (code "7") (name "Net-(C8-Pad2)") (class "Default")
      (node (ref "C8") (pin "2") (pinfunction "2_2") (pintype "passive"))
      (node (ref "JP10") (pin "3") (pinfunction "3_3") (pintype "passive"))
      (node (ref "R8") (pin "2") (pinfunction "2_2") (pintype "passive"))
    )
    (net (code "8") (name "Net-(C10-Pad2)") (class "Default")
      (node (ref "C10") (pin "2") (pinfunction "2_2") (pintype "passive"))
      (node (ref "JP13") (pin "3") (pinfunction "3_3") (pintype "passive"))
      (node (ref "R10") (pin "2") (pinfunction "2_2") (pintype "passive"))
    )
    (net (code "9") (name "Net-(C12-Pad2)") (class "Default")
      (node (ref "C12") (pin "2") (pinfunction "2_2") (pintype "passive"))
      (node (ref "JP16") (pin "3") (pinfunction "3_3") (pintype "passive"))
      (node (ref "R12") (pin "2") (pinfunction "2_2") (pintype "passive"))
    )
    (net (code "10") (name "Net-(C14-Pad2)") (class "Default")
      (node (ref "C14") (pin "2") (pinfunction "2_2") (pintype "passive"))
      (node (ref "JP19") (pin "3") (pinfunction "3_3") (pintype "passive"))
      (node (ref "R14") (pin "2") (pinfunction "2_2") (pintype "passive"))
    )
    (net (code "11") (name "Net-(C16-Pad2)") (class "Default")
      (node (ref "C16") (pin "2") (pinfunction "2_2") (pintype "passive"))
      (node (ref "JP22") (pin "3") (pinfunction "3_3") (pintype "passive"))
      (node (ref "R16") (pin "2") (pinfunction "2_2") (pintype "passive"))
    )
    (net (code "12") (name "Net-(C18-Pad2)") (class "Default")
      (node (ref "C18") (pin "2") (pinfunction "2_2") (pintype "passive"))
      (node (ref "JP25") (pin "3") (pinfunction "3_3") (pintype "passive"))
      (node (ref "R18") (pin "2") (pinfunction "2_2") (pintype "passive"))
    )
    (net (code "13") (name "Net-(IC1-VOUT)") (class "Default")
      (node (ref "IC1") (pin "3") (pinfunction "VOUT_3") (pintype "output"))
      (node (ref "R2") (pin "1") (pinfunction "1_1") (pintype "passive"))
    )
    (net (code "14") (name "Net-(IC3-VOUT)") (class "Default")
      (node (ref "IC3") (pin "3") (pinfunction "VOUT_3") (pintype "output"))
      (node (ref "R6") (pin "1") (pinfunction "1_1") (pintype "passive"))
    )
    (net (code "15") (name "Net-(IC4-VOUT)") (class "Default")
      (node (ref "IC4") (pin "3") (pinfunction "VOUT_3") (pintype "output"))
      (node (ref "R8") (pin "1") (pinfunction "1_1") (pintype "passive"))
    )
    (net (code "16") (name "Net-(IC5-VOUT)") (class "Default")
      (node (ref "IC5") (pin "3") (pinfunction "VOUT_3") (pintype "output"))
      (node (ref "R10") (pin "1") (pinfunction "1_1") (pintype "passive"))
    )
    (net (code "17") (name "Net-(IC6-VOUT)") (class "Default")
      (node (ref "IC6") (pin "3") (pinfunction "VOUT_3") (pintype "output"))
      (node (ref "R12") (pin "1") (pinfunction "1_1") (pintype "passive"))
    )
    (net (code "18") (name "Net-(IC7-VOUT)") (class "Default")
      (node (ref "IC7") (pin "3") (pinfunction "VOUT_3") (pintype "output"))
      (node (ref "R14") (pin "1") (pinfunction "1_1") (pintype "passive"))
    )
    (net (code "19") (name "Net-(IC8-VOUT)") (class "Default")
      (node (ref "IC8") (pin "3") (pinfunction "VOUT_3") (pintype "output"))
      (node (ref "R16") (pin "1") (pinfunction "1_1") (pintype "passive"))
    )
    (net (code "20") (name "Net-(IC9-VOUT)") (class "Default")
      (node (ref "IC9") (pin "3") (pinfunction "VOUT_3") (pintype "output"))
      (node (ref "R18") (pin "1") (pinfunction "1_1") (pintype "passive"))
    )
    (net (code "21") (name "Net-(LED1-PadA)") (class "Default")
      (node (ref "LED1") (pin "A") (pinfunction "A_A") (pintype "passive"))
      (node (ref "R1") (pin "2") (pinfunction "2_2") (pintype "passive"))
    )
    (net (code "22") (name "Net-(LED3-PadA)") (class "Default")
      (node (ref "LED3") (pin "A") (pinfunction "A_A") (pintype "passive"))
      (node (ref "R5") (pin "2") (pinfunction "2_2") (pintype "passive"))
    )
    (net (code "23") (name "Net-(LED4-PadA)") (class "Default")
      (node (ref "LED4") (pin "A") (pinfunction "A_A") (pintype "passive"))
      (node (ref "R7") (pin "2") (pinfunction "2_2") (pintype "passive"))
    )
    (net (code "24") (name "Net-(LED5-PadA)") (class "Default")
      (node (ref "LED5") (pin "A") (pinfunction "A_A") (pintype "passive"))
      (node (ref "R9") (pin "2") (pinfunction "2_2") (pintype "passive"))
    )
    (net (code "25") (name "Net-(LED6-PadA)") (class "Default")
      (node (ref "LED6") (pin "A") (pinfunction "A_A") (pintype "passive"))
      (node (ref "R11") (pin "2") (pinfunction "2_2") (pintype "passive"))
    )
    (net (code "26") (name "Net-(LED7-PadA)") (class "Default")
      (node (ref "LED7") (pin "A") (pinfunction "A_A") (pintype "passive"))
      (node (ref "R13") (pin "2") (pinfunction "2_2") (pintype "passive"))
    )
    (net (code "27") (name "Net-(LED8-PadA)") (class "Default")
      (node (ref "LED8") (pin "A") (pinfunction "A_A") (pintype "passive"))
      (node (ref "R15") (pin "2") (pinfunction "2_2") (pintype "passive"))
    )
    (net (code "28") (name "Net-(LED9-PadA)") (class "Default")
      (node (ref "LED9") (pin "A") (pinfunction "A_A") (pintype "passive"))
      (node (ref "R17") (pin "2") (pinfunction "2_2") (pintype "passive"))
    )
  )
)
